# OpenBook.net
KiCad netlist of a schematic drawn in EAGLE
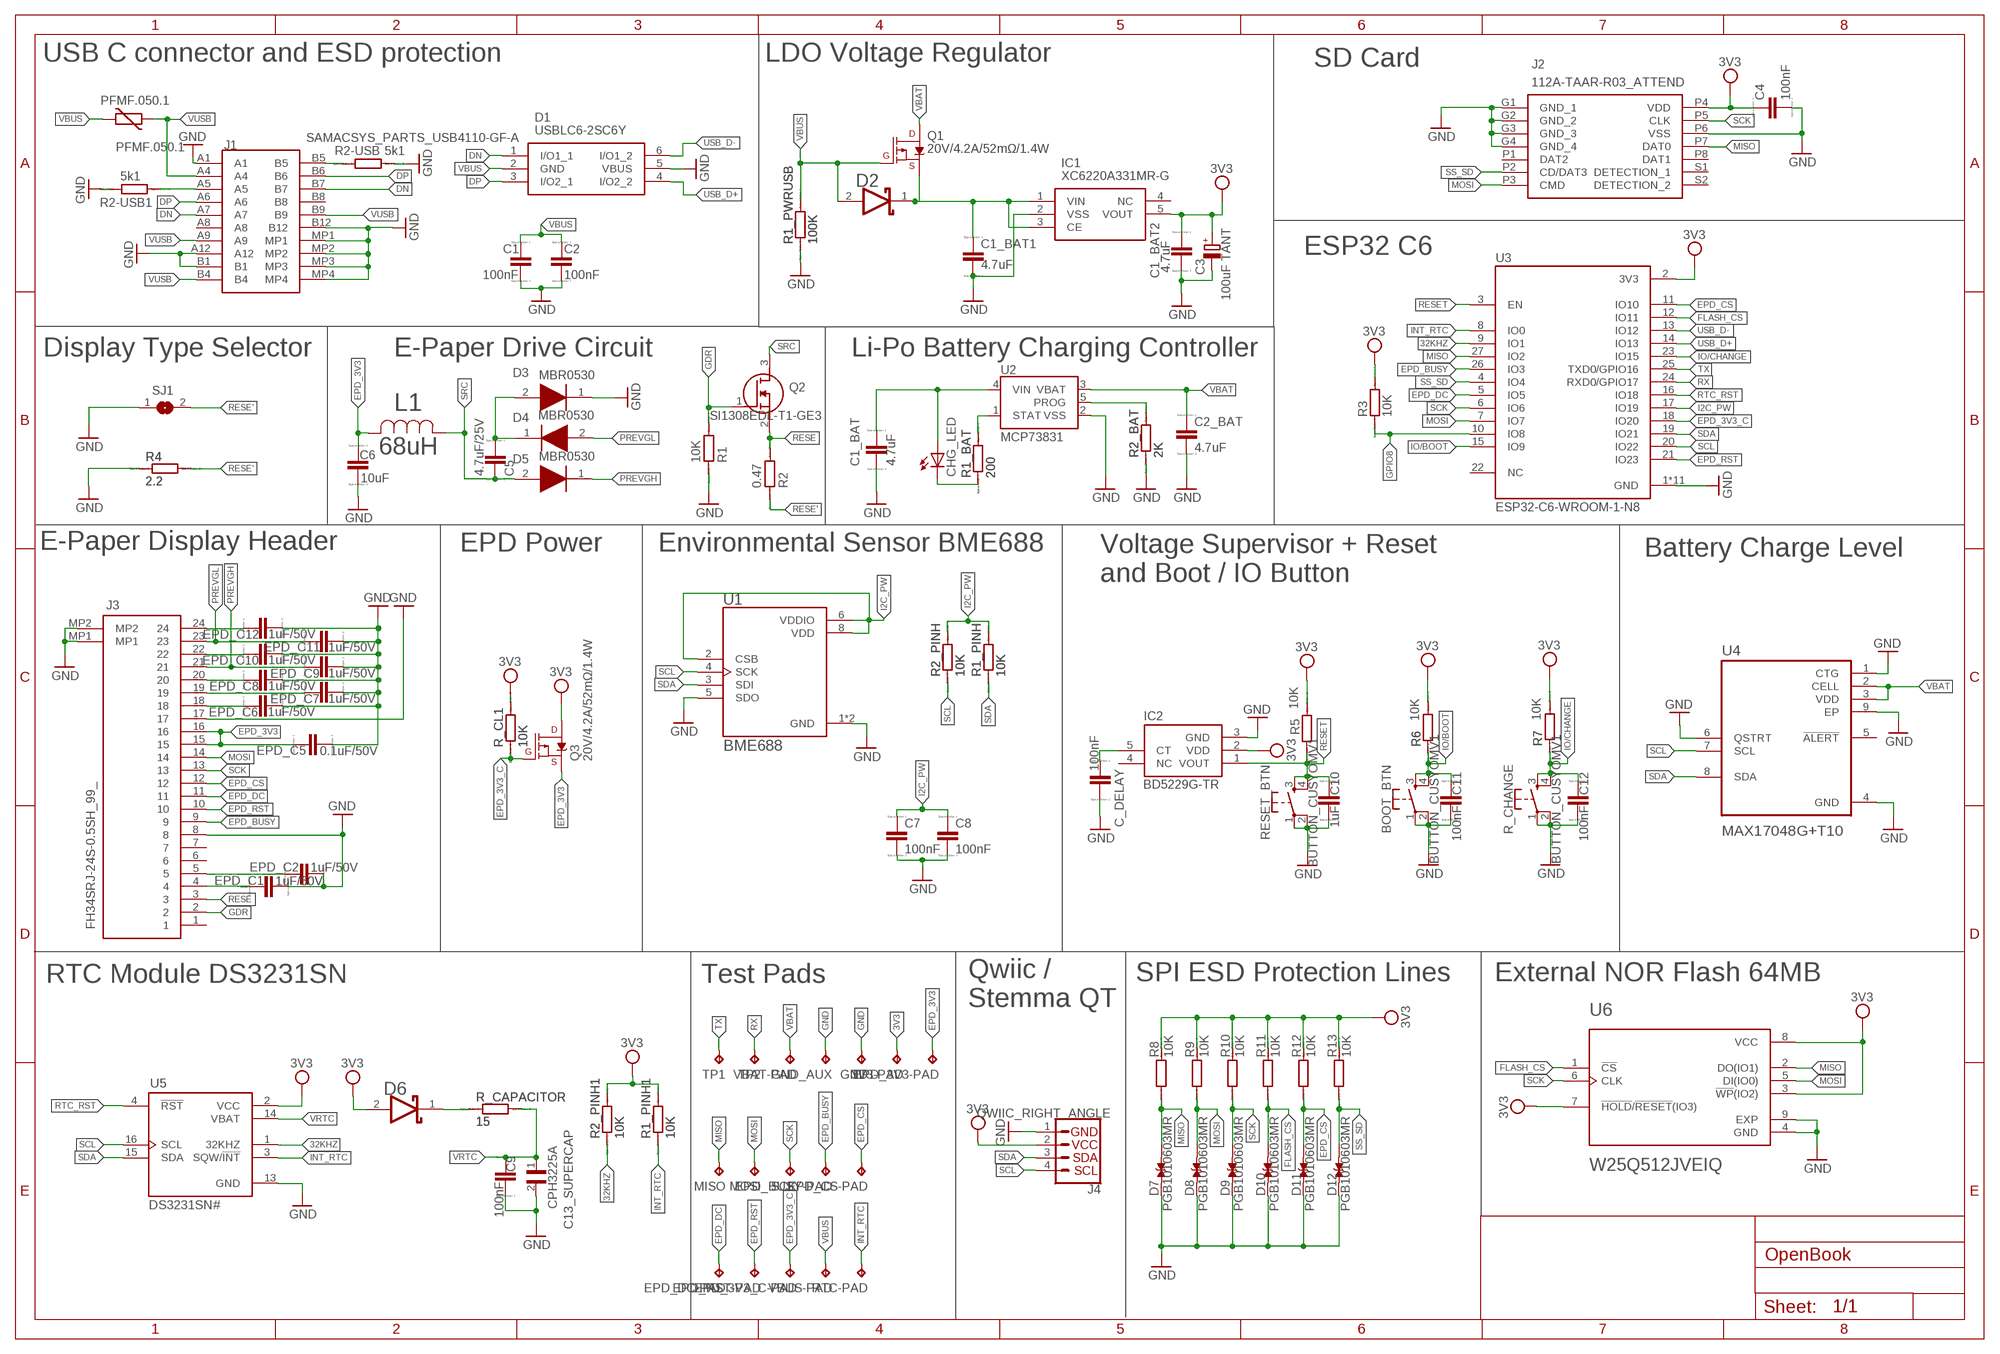
[diagram p0: schematic, sheet 1]

(export (version "E")
  (design (tool "Eeschema 10.0.6"))
  (components
    (comp (ref "3V3-PAD")
      (value "TPTP20R")
      (footprint "eagle-import:TP20R")
      (libsource (lib "eagle-import") (part "TPTP20R"))
    )
    (comp (ref "BOOT_BTN")
      (value "BUTTON_CUSYOMV1")
      (footprint "eagle-import:MYBUTTON")
      (libsource (lib "eagle-import") (part "BUTTON_CUSYOMV1"))
    )
    (comp (ref "C1")
      (value "100nF")
      (footprint "eagle-import:ESP32_WROVER_EAGLE-LTSPICE_C0402")
      (libsource (lib "eagle-import") (part "ESP32_WROVER_EAGLE-LTSPICE_CC0402"))
    )
    (comp (ref "C1_BAT")
      (value "4.7uF")
      (footprint "eagle-import:EAGLE-LTSPICE_C0402")
      (libsource (lib "eagle-import") (part "EAGLE-LTSPICE_CC0402"))
    )
    (comp (ref "C1_BAT1")
      (value "4.7uF")
      (footprint "eagle-import:EAGLE-LTSPICE_C0402")
      (libsource (lib "eagle-import") (part "EAGLE-LTSPICE_CC0402"))
    )
    (comp (ref "C1_BAT2")
      (value "4.7uF")
      (footprint "eagle-import:EAGLE-LTSPICE_C0402")
      (libsource (lib "eagle-import") (part "EAGLE-LTSPICE_CC0402"))
    )
    (comp (ref "C2")
      (value "100nF")
      (footprint "eagle-import:ESP32_WROVER_EAGLE-LTSPICE_C0402")
      (libsource (lib "eagle-import") (part "ESP32_WROVER_EAGLE-LTSPICE_CC0402"))
    )
    (comp (ref "C2_BAT")
      (value "4.7uF")
      (footprint "eagle-import:EAGLE-LTSPICE_C0402")
      (libsource (lib "eagle-import") (part "EAGLE-LTSPICE_CC0402"))
    )
    (comp (ref "C3")
      (value "100uF TANT")
      (footprint "eagle-import:RCL_CT3528")
      (libsource (lib "eagle-import") (part "RCL_CPOL-EUCT3528"))
    )
    (comp (ref "C4")
      (value "100nF")
      (footprint "eagle-import:EAGLE-LTSPICE_C0402")
      (libsource (lib "eagle-import") (part "EAGLE-LTSPICE_CC0402"))
    )
    (comp (ref "C5")
      (value "4.7uF/25V")
      (footprint "eagle-import:ESP32_WROVER_EAGLE-LTSPICE_C0402")
      (libsource (lib "eagle-import") (part "ESP32_WROVER_EAGLE-LTSPICE_CC0402"))
    )
    (comp (ref "C6")
      (value "10uF")
      (footprint "eagle-import:ESP32_WROVER_EAGLE-LTSPICE_C0402")
      (libsource (lib "eagle-import") (part "ESP32_WROVER_EAGLE-LTSPICE_CC0402"))
    )
    (comp (ref "C7")
      (value "100nF")
      (footprint "eagle-import:EAGLE-LTSPICE_C0402")
      (libsource (lib "eagle-import") (part "EAGLE-LTSPICE_CC0402"))
    )
    (comp (ref "C8")
      (value "100nF")
      (footprint "eagle-import:EAGLE-LTSPICE_C0402")
      (libsource (lib "eagle-import") (part "EAGLE-LTSPICE_CC0402"))
    )
    (comp (ref "C9")
      (value "100nF")
      (footprint "eagle-import:EAGLE-LTSPICE_C0402")
      (libsource (lib "eagle-import") (part "EAGLE-LTSPICE_CC0402"))
    )
    (comp (ref "C10")
      (value "1uF")
      (footprint "eagle-import:EAGLE-LTSPICE_C0402")
      (libsource (lib "eagle-import") (part "EAGLE-LTSPICE_CC0402"))
    )
    (comp (ref "C11")
      (value "100nF")
      (footprint "eagle-import:EAGLE-LTSPICE_C0402")
      (libsource (lib "eagle-import") (part "EAGLE-LTSPICE_CC0402"))
    )
    (comp (ref "C12")
      (value "100nF")
      (footprint "eagle-import:EAGLE-LTSPICE_C0402")
      (libsource (lib "eagle-import") (part "EAGLE-LTSPICE_CC0402"))
    )
    (comp (ref "C13_SUPERCAP")
      (value "CPH3225A")
      (footprint "eagle-import:CAPCP3225X100N")
      (fields (field (name "MF") "Seiko Instruments"))
      (libsource (lib "eagle-import") (part "CPH3225A"))
    )
    (comp (ref "CHG_LED")
      (value "ADAFRUIT_LEDCHIP-LED0603")
      (footprint "eagle-import:ADAFRUIT_CHIP-LED0603")
      (libsource (lib "eagle-import") (part "ADAFRUIT_LEDCHIP-LED0603"))
    )
    (comp (ref "C_DELAY")
      (value "100nF")
      (footprint "eagle-import:EAGLE-LTSPICE_C0402")
      (libsource (lib "eagle-import") (part "EAGLE-LTSPICE_CC0402"))
    )
    (comp (ref "D1")
      (value "USBLC6-2SC6Y")
      (footprint "eagle-import:SOT95P280X145-6N")
      (fields (field (name "MF") "STMicroelectronics"))
      (libsource (lib "eagle-import") (part "USBLC6-2SC6Y"))
    )
    (comp (ref "D2")
      (value "ESP32_WROVER_AVX---SD0805S020S1R0_AVX_SD0805S020S1R0_0_0AVX_SD0805S020S1R0_0_0")
      (footprint "eagle-import:ESP32_WROVER_AVX---SD0805S020S1R0_AVX_SD0805S020S1R0_0")
      (fields
        (field (name "DIGIKEY_PART_NUMBER") "478-7800-1-ND")
        (field (name "MF") "AVX")
        (field (name "MOUSER_PART_NUMBER") "581-SD0805S020S1R0")
      )
      (libsource (lib "eagle-import") (part "ESP32_WROVER_AVX---SD0805S020S1R0_AVX_SD0805S020S1R0_0_0AVX_SD0805S020S1R0_0_0"))
    )
    (comp (ref "D3")
      (value "MBR0530")
      (footprint "eagle-import:SOD3716X135N")
      (fields (field (name "MF") "ON Semiconductor"))
      (libsource (lib "eagle-import") (part "MBR0530"))
    )
    (comp (ref "D4")
      (value "MBR0530")
      (footprint "eagle-import:SOD3716X135N")
      (fields (field (name "MF") "ON Semiconductor"))
      (libsource (lib "eagle-import") (part "MBR0530"))
    )
    (comp (ref "D5")
      (value "MBR0530")
      (footprint "eagle-import:SOD3716X135N")
      (fields (field (name "MF") "ON Semiconductor"))
      (libsource (lib "eagle-import") (part "MBR0530"))
    )
    (comp (ref "D6")
      (value "ESP32_WROVER_AVX---SD0805S020S1R0_AVX_SD0805S020S1R0_0_0AVX_SD0805S020S1R0_0_0")
      (footprint "eagle-import:ESP32_WROVER_AVX---SD0805S020S1R0_AVX_SD0805S020S1R0_0")
      (fields
        (field (name "DIGIKEY_PART_NUMBER") "478-7800-1-ND")
        (field (name "MF") "AVX")
        (field (name "MOUSER_PART_NUMBER") "581-SD0805S020S1R0")
      )
      (libsource (lib "eagle-import") (part "ESP32_WROVER_AVX---SD0805S020S1R0_AVX_SD0805S020S1R0_0_0AVX_SD0805S020S1R0_0_0"))
    )
    (comp (ref "D7")
      (value "PGB1010603MR")
      (footprint "eagle-import:DIOC1608X36N")
      (fields (field (name "MF") "Littelfuse Inc."))
      (libsource (lib "eagle-import") (part "PGB1010603MR"))
    )
    (comp (ref "D8")
      (value "PGB1010603MR")
      (footprint "eagle-import:DIOC1608X36N")
      (fields (field (name "MF") "Littelfuse Inc."))
      (libsource (lib "eagle-import") (part "PGB1010603MR"))
    )
    (comp (ref "D9")
      (value "PGB1010603MR")
      (footprint "eagle-import:DIOC1608X36N")
      (fields (field (name "MF") "Littelfuse Inc."))
      (libsource (lib "eagle-import") (part "PGB1010603MR"))
    )
    (comp (ref "D10")
      (value "PGB1010603MR")
      (footprint "eagle-import:DIOC1608X36N")
      (fields (field (name "MF") "Littelfuse Inc."))
      (libsource (lib "eagle-import") (part "PGB1010603MR"))
    )
    (comp (ref "D11")
      (value "PGB1010603MR")
      (footprint "eagle-import:DIOC1608X36N")
      (fields (field (name "MF") "Littelfuse Inc."))
      (libsource (lib "eagle-import") (part "PGB1010603MR"))
    )
    (comp (ref "D12")
      (value "PGB1010603MR")
      (footprint "eagle-import:DIOC1608X36N")
      (fields (field (name "MF") "Littelfuse Inc."))
      (libsource (lib "eagle-import") (part "PGB1010603MR"))
    )
    (comp (ref "EPD_3V3-PAD")
      (value "TPTP20R")
      (footprint "eagle-import:TP20R")
      (libsource (lib "eagle-import") (part "TPTP20R"))
    )
    (comp (ref "EPD_3V3_C-PAD")
      (value "TPTP20R")
      (footprint "eagle-import:TP20R")
      (libsource (lib "eagle-import") (part "TPTP20R"))
    )
    (comp (ref "EPD_BUSY-PAD")
      (value "TPTP20R")
      (footprint "eagle-import:TP20R")
      (libsource (lib "eagle-import") (part "TPTP20R"))
    )
    (comp (ref "EPD_C1")
      (value "1uF/50V")
      (footprint "eagle-import:ESP32_WROVER_EAGLE-LTSPICE_C0402")
      (libsource (lib "eagle-import") (part "ESP32_WROVER_EAGLE-LTSPICE_CC0402"))
    )
    (comp (ref "EPD_C2")
      (value "1uF/50V")
      (footprint "eagle-import:ESP32_WROVER_EAGLE-LTSPICE_C0402")
      (libsource (lib "eagle-import") (part "ESP32_WROVER_EAGLE-LTSPICE_CC0402"))
    )
    (comp (ref "EPD_C5")
      (value "0.1uF/50V")
      (footprint "eagle-import:ESP32_WROVER_EAGLE-LTSPICE_C0402")
      (libsource (lib "eagle-import") (part "ESP32_WROVER_EAGLE-LTSPICE_CC0402"))
    )
    (comp (ref "EPD_C6")
      (value "1uF/50V")
      (footprint "eagle-import:ESP32_WROVER_EAGLE-LTSPICE_C0402")
      (libsource (lib "eagle-import") (part "ESP32_WROVER_EAGLE-LTSPICE_CC0402"))
    )
    (comp (ref "EPD_C7")
      (value "1uF/50V")
      (footprint "eagle-import:ESP32_WROVER_EAGLE-LTSPICE_C0402")
      (libsource (lib "eagle-import") (part "ESP32_WROVER_EAGLE-LTSPICE_CC0402"))
    )
    (comp (ref "EPD_C8")
      (value "1uF/50V")
      (footprint "eagle-import:ESP32_WROVER_EAGLE-LTSPICE_C0402")
      (libsource (lib "eagle-import") (part "ESP32_WROVER_EAGLE-LTSPICE_CC0402"))
    )
    (comp (ref "EPD_C9")
      (value "1uF/50V")
      (footprint "eagle-import:ESP32_WROVER_EAGLE-LTSPICE_C0402")
      (libsource (lib "eagle-import") (part "ESP32_WROVER_EAGLE-LTSPICE_CC0402"))
    )
    (comp (ref "EPD_C10")
      (value "1uF/50V")
      (footprint "eagle-import:ESP32_WROVER_EAGLE-LTSPICE_C0402")
      (libsource (lib "eagle-import") (part "ESP32_WROVER_EAGLE-LTSPICE_CC0402"))
    )
    (comp (ref "EPD_C11")
      (value "1uF/50V")
      (footprint "eagle-import:ESP32_WROVER_EAGLE-LTSPICE_C0402")
      (libsource (lib "eagle-import") (part "ESP32_WROVER_EAGLE-LTSPICE_CC0402"))
    )
    (comp (ref "EPD_C12")
      (value "1uF/50V")
      (footprint "eagle-import:ESP32_WROVER_EAGLE-LTSPICE_C0402")
      (libsource (lib "eagle-import") (part "ESP32_WROVER_EAGLE-LTSPICE_CC0402"))
    )
    (comp (ref "EPD_CS-PAD")
      (value "TPTP20R")
      (footprint "eagle-import:TP20R")
      (libsource (lib "eagle-import") (part "TPTP20R"))
    )
    (comp (ref "EPD_DC-PAD")
      (value "TPTP20R")
      (footprint "eagle-import:TP20R")
      (libsource (lib "eagle-import") (part "TPTP20R"))
    )
    (comp (ref "EPD_RST-PAD")
      (value "TPTP20R")
      (footprint "eagle-import:TP20R")
      (libsource (lib "eagle-import") (part "TPTP20R"))
    )
    (comp (ref "GND")
      (value "TPTP20R")
      (footprint "eagle-import:TP20R")
      (libsource (lib "eagle-import") (part "TPTP20R"))
    )
    (comp (ref "GND_AUX")
      (value "TPTP20R")
      (footprint "eagle-import:TP20R")
      (libsource (lib "eagle-import") (part "TPTP20R"))
    )
    (comp (ref "IC1")
      (value "XC6220A331MR-G")
      (footprint "eagle-import:SOT95P280X120-5N")
      (fields (field (name "MOUSER_PART_NUMBER") "865-XC6220A331MR-G"))
      (libsource (lib "eagle-import") (part "XC6220A331MR-G"))
    )
    (comp (ref "IC2")
      (value "BD5229G-TR")
      (footprint "eagle-import:SOT95P280X125-5N")
      (fields (field (name "MOUSER_PART_NUMBER") "755-BD5229G-TR"))
      (libsource (lib "eagle-import") (part "BD5229G-TR"))
    )
    (comp (ref "J1")
      (value "SAMACSYS_PARTS_USB4110-GF-A")
      (footprint "eagle-import:SAMACSYS_PARTS_USB4110GFA")
      (fields
        (field (name "MANUFACTURER_PART_NUMBER") "USB4110-GF-A")
        (field (name "MOUSER_PART_NUMBER") "640-USB4110-GF-A")
      )
      (libsource (lib "eagle-import") (part "SAMACSYS_PARTS_USB4110-GF-A"))
    )
    (comp (ref "J2")
      (value "112A-TAAR-R03_ATTEND")
      (footprint "eagle-import:112ATAARR03ATTEND")
      (fields (field (name "MANUFACTURER_PART_NUMBER") "112A-TAAR-R03 ATTEND"))
      (libsource (lib "eagle-import") (part "112A-TAAR-R03_ATTEND"))
    )
    (comp (ref "J3")
      (value "FH34SRJ-24S-0.5SH_99_")
      (footprint "eagle-import:FH34SRJ24S05SH99")
      (fields
        (field (name "MANUFACTURER_PART_NUMBER") "FH34SRJ-24S-0.5SH(99)")
        (field (name "MOUSER_PART_NUMBER") "798-FH34SRJ24S05SH99")
      )
      (libsource (lib "eagle-import") (part "FH34SRJ-24S-0.5SH_99_"))
    )
    (comp (ref "J4")
      (value "QWIIC_RIGHT_ANGLE")
      (footprint "eagle-import:JST04_1MM_RA")
      (libsource (lib "eagle-import") (part "QWIIC_CONNECTORJS-1MM"))
    )
    (comp (ref "L1")
      (value "68uH")
      (footprint "eagle-import:IND_4828-WE-TPC_WRE")
      (fields
        (field (name "MANUFACTURER_PART_NUMBER") "744043680")
        (field (name "COPYRIGHT") "Copyright (C) 2024 Ultra Librarian. All rights reserved.")
      )
      (libsource (lib "eagle-import") (part "744043680IND_4828-WE-TPC_WRE"))
    )
    (comp (ref "MISO")
      (value "TPTP20R")
      (footprint "eagle-import:TP20R")
      (libsource (lib "eagle-import") (part "TPTP20R"))
    )
    (comp (ref "MOSI")
      (value "TPTP20R")
      (footprint "eagle-import:TP20R")
      (libsource (lib "eagle-import") (part "TPTP20R"))
    )
    (comp (ref "PFMF.050.1")
      (value "PFMF.050.1")
      (footprint "eagle-import:ESP32C6_VARISTOR_CT_CN1812")
      (libsource (lib "eagle-import") (part "ESP32C6_VARISTORCN1812"))
    )
    (comp (ref "Q1")
      (value "20V/4.2A/52mΩ/1.4W")
      (footprint "eagle-import:ESP32_WROVER_SPARKFUN-DISCRETESEMI_SOT23-3")
      (libsource (lib "eagle-import") (part "ESP32_WROVER_SPARKFUN-DISCRETESEMI_MOSFET_PCH-DMG2305UX-7"))
    )
    (comp (ref "Q2")
      (value "SI1308EDL-T1-GE3")
      (footprint "eagle-import:SOT65P210X110-3N")
      (fields (field (name "MF") "Vishay Siliconix"))
      (libsource (lib "eagle-import") (part "SI1308EDL-T1-GE3"))
    )
    (comp (ref "Q3")
      (value "20V/4.2A/52mΩ/1.4W")
      (footprint "eagle-import:ESP32_WROVER_SPARKFUN-DISCRETESEMI_SOT23-3")
      (libsource (lib "eagle-import") (part "ESP32_WROVER_SPARKFUN-DISCRETESEMI_MOSFET_PCH-DMG2305UX-7"))
    )
    (comp (ref "R1")
      (value "10K")
      (footprint "eagle-import:ESP32_WROVER_EAGLE-LTSPICE_R0402")
      (libsource (lib "eagle-import") (part "ESP32_WROVER_EAGLE-LTSPICE_RR0402"))
    )
    (comp (ref "R1_BAT")
      (value "200")
      (footprint "eagle-import:ESP32_WROVER_EAGLE-LTSPICE_R0402")
      (libsource (lib "eagle-import") (part "ESP32_WROVER_EAGLE-LTSPICE_RR0402"))
    )
    (comp (ref "R1_PINH")
      (value "10K")
      (footprint "eagle-import:ESP32_WROVER_EAGLE-LTSPICE_R0402")
      (libsource (lib "eagle-import") (part "ESP32_WROVER_EAGLE-LTSPICE_RR0402"))
    )
    (comp (ref "R1_PINH1")
      (value "10K")
      (footprint "eagle-import:ESP32_WROVER_EAGLE-LTSPICE_R0402")
      (libsource (lib "eagle-import") (part "ESP32_WROVER_EAGLE-LTSPICE_RR0402"))
    )
    (comp (ref "R1_PWRUSB")
      (value "100K")
      (footprint "eagle-import:ESP32_WROVER_EAGLE-LTSPICE_R0402")
      (libsource (lib "eagle-import") (part "ESP32_WROVER_EAGLE-LTSPICE_RR0402"))
    )
    (comp (ref "R2")
      (value "0.47")
      (footprint "eagle-import:ESP32_WROVER_EAGLE-LTSPICE_R0402")
      (libsource (lib "eagle-import") (part "ESP32_WROVER_EAGLE-LTSPICE_RR0402"))
    )
    (comp (ref "R2-USB")
      (value "5k1")
      (footprint "eagle-import:ESP32_WROVER_EAGLE-LTSPICE_R0402")
      (libsource (lib "eagle-import") (part "ESP32_WROVER_EAGLE-LTSPICE_RR0402"))
    )
    (comp (ref "R2-USB1")
      (value "5k1")
      (footprint "eagle-import:ESP32_WROVER_EAGLE-LTSPICE_R0402")
      (libsource (lib "eagle-import") (part "ESP32_WROVER_EAGLE-LTSPICE_RR0402"))
    )
    (comp (ref "R2_BAT")
      (value "2K")
      (footprint "eagle-import:ESP32_WROVER_EAGLE-LTSPICE_R0402")
      (libsource (lib "eagle-import") (part "ESP32_WROVER_EAGLE-LTSPICE_RR0402"))
    )
    (comp (ref "R2_PINH")
      (value "10K")
      (footprint "eagle-import:ESP32_WROVER_EAGLE-LTSPICE_R0402")
      (libsource (lib "eagle-import") (part "ESP32_WROVER_EAGLE-LTSPICE_RR0402"))
    )
    (comp (ref "R2_PINH1")
      (value "10K")
      (footprint "eagle-import:ESP32_WROVER_EAGLE-LTSPICE_R0402")
      (libsource (lib "eagle-import") (part "ESP32_WROVER_EAGLE-LTSPICE_RR0402"))
    )
    (comp (ref "R3")
      (value "10K")
      (footprint "eagle-import:ESP32_WROVER_EAGLE-LTSPICE_R0402")
      (libsource (lib "eagle-import") (part "ESP32_WROVER_EAGLE-LTSPICE_RR0402"))
    )
    (comp (ref "R4")
      (value "2.2")
      (footprint "eagle-import:ESP32_WROVER_EAGLE-LTSPICE_R0402")
      (libsource (lib "eagle-import") (part "ESP32_WROVER_EAGLE-LTSPICE_RR0402"))
    )
    (comp (ref "R5")
      (value "10K")
      (footprint "eagle-import:ESP32_WROVER_EAGLE-LTSPICE_R0402")
      (libsource (lib "eagle-import") (part "ESP32_WROVER_EAGLE-LTSPICE_RR0402"))
    )
    (comp (ref "R6")
      (value "10K")
      (footprint "eagle-import:ESP32_WROVER_EAGLE-LTSPICE_R0402")
      (libsource (lib "eagle-import") (part "ESP32_WROVER_EAGLE-LTSPICE_RR0402"))
    )
    (comp (ref "R7")
      (value "10K")
      (footprint "eagle-import:ESP32_WROVER_EAGLE-LTSPICE_R0402")
      (libsource (lib "eagle-import") (part "ESP32_WROVER_EAGLE-LTSPICE_RR0402"))
    )
    (comp (ref "R8")
      (value "10K")
      (footprint "eagle-import:ESP32_WROVER_EAGLE-LTSPICE_R0402")
      (libsource (lib "eagle-import") (part "ESP32_WROVER_EAGLE-LTSPICE_RR0402"))
    )
    (comp (ref "R9")
      (value "10K")
      (footprint "eagle-import:ESP32_WROVER_EAGLE-LTSPICE_R0402")
      (libsource (lib "eagle-import") (part "ESP32_WROVER_EAGLE-LTSPICE_RR0402"))
    )
    (comp (ref "R10")
      (value "10K")
      (footprint "eagle-import:ESP32_WROVER_EAGLE-LTSPICE_R0402")
      (libsource (lib "eagle-import") (part "ESP32_WROVER_EAGLE-LTSPICE_RR0402"))
    )
    (comp (ref "R11")
      (value "10K")
      (footprint "eagle-import:ESP32_WROVER_EAGLE-LTSPICE_R0402")
      (libsource (lib "eagle-import") (part "ESP32_WROVER_EAGLE-LTSPICE_RR0402"))
    )
    (comp (ref "R12")
      (value "10K")
      (footprint "eagle-import:ESP32_WROVER_EAGLE-LTSPICE_R0402")
      (libsource (lib "eagle-import") (part "ESP32_WROVER_EAGLE-LTSPICE_RR0402"))
    )
    (comp (ref "R13")
      (value "10K")
      (footprint "eagle-import:ESP32_WROVER_EAGLE-LTSPICE_R0402")
      (libsource (lib "eagle-import") (part "ESP32_WROVER_EAGLE-LTSPICE_RR0402"))
    )
    (comp (ref "RESET_BTN")
      (value "BUTTON_CUSYOMV1")
      (footprint "eagle-import:MYBUTTON")
      (libsource (lib "eagle-import") (part "BUTTON_CUSYOMV1"))
    )
    (comp (ref "RTC-PAD")
      (value "TPTP20R")
      (footprint "eagle-import:TP20R")
      (libsource (lib "eagle-import") (part "TPTP20R"))
    )
    (comp (ref "R_CAPACITOR")
      (value "15")
      (footprint "eagle-import:ESP32_WROVER_EAGLE-LTSPICE_R0402")
      (libsource (lib "eagle-import") (part "ESP32_WROVER_EAGLE-LTSPICE_RR0402"))
    )
    (comp (ref "R_CHANGE")
      (value "BUTTON_CUSYOMV1")
      (footprint "eagle-import:MYBUTTON")
      (libsource (lib "eagle-import") (part "BUTTON_CUSYOMV1"))
    )
    (comp (ref "R_CL1")
      (value "10K")
      (footprint "eagle-import:ESP32_WROVER_EAGLE-LTSPICE_R0402")
      (libsource (lib "eagle-import") (part "ESP32_WROVER_EAGLE-LTSPICE_RR0402"))
    )
    (comp (ref "SCK")
      (value "TPTP20R")
      (footprint "eagle-import:TP20R")
      (libsource (lib "eagle-import") (part "TPTP20R"))
    )
    (comp (ref "SJ1") (value "SJ") (footprint "eagle-import:SJ") (libsource (lib "eagle-import") (part "SJ")))
    (comp (ref "TP1")
      (value "TPTP20R")
      (footprint "eagle-import:TP20R")
      (libsource (lib "eagle-import") (part "TPTP20R"))
    )
    (comp (ref "TP2")
      (value "TPTP20R")
      (footprint "eagle-import:TP20R")
      (libsource (lib "eagle-import") (part "TPTP20R"))
    )
    (comp (ref "U1")
      (value "BME688")
      (footprint "eagle-import:ESP32_WROVER_BME680_PSON80P300X300X100-8N")
      (fields (field (name "MF") "Bosch Sensortec") (field (name "MP") "BME680"))
      (libsource (lib "eagle-import") (part "ESP32_WROVER_BME680_BME680"))
    )
    (comp (ref "U2")
      (value "MCP73831")
      (footprint "eagle-import:ESP32_WROVER_SPARKFUN-IC-POWER_SOT23-5")
      (libsource (lib "eagle-import") (part "ESP32_WROVER_SPARKFUN-IC-POWER_MCP73831"))
    )
    (comp (ref "U3")
      (value "ESP32-C6-WROOM-1-N8")
      (footprint "eagle-import:XCVR_ESP32-C6-WROOM-1-N8")
      (fields (field (name "MF") "Espressif Systems"))
      (libsource (lib "eagle-import") (part "ESP32-C6-WROOM-1-N8"))
    )
    (comp (ref "U4")
      (value "MAX17048G+T10")
      (footprint "eagle-import:SON50P200X200X80-9N")
      (fields (field (name "MF") "Analog Devices"))
      (libsource (lib "eagle-import") (part "MAX17048G+T10"))
    )
    (comp (ref "U5")
      (value "DS3231SN#")
      (footprint "eagle-import:SOIC127P1032X265-16N")
      (fields (field (name "MF") "Analog Devices"))
      (libsource (lib "eagle-import") (part "DS3231SN#"))
    )
    (comp (ref "U6")
      (value "W25Q512JVEIQ")
      (footprint "eagle-import:SON127P600X800X80-9N")
      (fields (field (name "MF") "Winbond Electronics"))
      (libsource (lib "eagle-import") (part "W25Q512JVEIQ"))
    )
    (comp (ref "VBAT-PAD")
      (value "TPTP20R")
      (footprint "eagle-import:TP20R")
      (libsource (lib "eagle-import") (part "TPTP20R"))
    )
    (comp (ref "VBUS-PAD")
      (value "TPTP20R")
      (footprint "eagle-import:TP20R")
      (libsource (lib "eagle-import") (part "TPTP20R"))
    )
  )
  (nets
    (net (code "1") (name "3V3") (class "Default")
      (node (ref "3V3-PAD") (pin "TP") (pinfunction "TP_TP") (pintype "input"))
      (node (ref "C1_BAT2") (pin "1") (pinfunction "1_1") (pintype "passive"))
      (node (ref "C3") (pin "+") (pinfunction "+_+") (pintype "passive"))
      (node (ref "C4") (pin "1") (pinfunction "1_1") (pintype "passive"))
      (node (ref "D6") (pin "2") (pinfunction "ANODE_2") (pintype "bidirectional"))
      (node (ref "IC1") (pin "5") (pinfunction "VOUT_5") (pintype "bidirectional"))
      (node (ref "IC2") (pin "2") (pinfunction "VDD_2") (pintype "bidirectional"))
      (node (ref "J2") (pin "P4") (pinfunction "VDD_P4") (pintype "bidirectional"))
      (node (ref "J4") (pin "2") (pinfunction "2_2") (pintype "power_in"))
      (node (ref "Q3") (pin "3") (pinfunction "D_3") (pintype "bidirectional"))
      (node (ref "R10") (pin "2") (pinfunction "2_2") (pintype "passive"))
      (node (ref "R11") (pin "2") (pinfunction "2_2") (pintype "passive"))
      (node (ref "R12") (pin "2") (pinfunction "2_2") (pintype "passive"))
      (node (ref "R13") (pin "2") (pinfunction "2_2") (pintype "passive"))
      (node (ref "R1_PINH1") (pin "2") (pinfunction "2_2") (pintype "passive"))
      (node (ref "R2_PINH1") (pin "2") (pinfunction "2_2") (pintype "passive"))
      (node (ref "R3") (pin "2") (pinfunction "2_2") (pintype "passive"))
      (node (ref "R5") (pin "2") (pinfunction "2_2") (pintype "passive"))
      (node (ref "R6") (pin "2") (pinfunction "2_2") (pintype "passive"))
      (node (ref "R7") (pin "2") (pinfunction "2_2") (pintype "passive"))
      (node (ref "R8") (pin "2") (pinfunction "2_2") (pintype "passive"))
      (node (ref "R9") (pin "2") (pinfunction "2_2") (pintype "passive"))
      (node (ref "R_CL1") (pin "2") (pinfunction "2_2") (pintype "passive"))
      (node (ref "U3") (pin "2") (pinfunction "3V3_2") (pintype "power_in"))
      (node (ref "U5") (pin "2") (pinfunction "VCC_2") (pintype "power_in"))
      (node (ref "U6") (pin "3") (pinfunction "~{WP}(IO2)_3") (pintype "bidirectional"))
      (node (ref "U6") (pin "7") (pinfunction "~{HOLD}/~{RESET}(IO3)_7") (pintype "bidirectional"))
      (node (ref "U6") (pin "8") (pinfunction "VCC_8") (pintype "power_in"))
    )
    (net (code "2") (name "32KHZ") (class "Default")
      (node (ref "R2_PINH1") (pin "1") (pinfunction "1_1") (pintype "passive"))
      (node (ref "U3") (pin "9") (pinfunction "IO1_9") (pintype "bidirectional"))
      (node (ref "U5") (pin "1") (pinfunction "32KHZ_1") (pintype "output"))
    )
    (net (code "3") (name "DN") (class "Default")
      (node (ref "D1") (pin "1") (pinfunction "I/O1_1_1") (pintype "bidirectional"))
      (node (ref "J1") (pin "A7") (pinfunction "A7_A7") (pintype "bidirectional"))
      (node (ref "J1") (pin "B7") (pinfunction "B7_B7") (pintype "bidirectional"))
    )
    (net (code "4") (name "DP") (class "Default")
      (node (ref "D1") (pin "3") (pinfunction "I/O2_1_3") (pintype "bidirectional"))
      (node (ref "J1") (pin "A6") (pinfunction "A6_A6") (pintype "bidirectional"))
      (node (ref "J1") (pin "B6") (pinfunction "B6_B6") (pintype "bidirectional"))
    )
    (net (code "5") (name "EPD_3V3") (class "Default")
      (node (ref "C6") (pin "1") (pinfunction "1_1") (pintype "passive"))
      (node (ref "EPD_3V3-PAD") (pin "TP") (pinfunction "TP_TP") (pintype "input"))
      (node (ref "EPD_C5") (pin "1") (pinfunction "1_1") (pintype "passive"))
      (node (ref "J3") (pin "15") (pinfunction "15_15") (pintype "bidirectional"))
      (node (ref "J3") (pin "16") (pinfunction "16_16") (pintype "bidirectional"))
      (node (ref "L1") (pin "2") (pinfunction "2_2") (pintype "passive"))
      (node (ref "Q3") (pin "2") (pinfunction "S_2") (pintype "bidirectional"))
    )
    (net (code "6") (name "EPD_3V3_C") (class "Default")
      (node (ref "EPD_3V3_C-PAD") (pin "TP") (pinfunction "TP_TP") (pintype "input"))
      (node (ref "Q3") (pin "1") (pinfunction "G_1") (pintype "bidirectional"))
      (node (ref "R_CL1") (pin "1") (pinfunction "1_1") (pintype "passive"))
      (node (ref "U3") (pin "18") (pinfunction "IO20_18") (pintype "bidirectional"))
    )
    (net (code "7") (name "EPD_BUSY") (class "Default")
      (node (ref "EPD_BUSY-PAD") (pin "TP") (pinfunction "TP_TP") (pintype "input"))
      (node (ref "J3") (pin "9") (pinfunction "9_9") (pintype "bidirectional"))
      (node (ref "U3") (pin "26") (pinfunction "IO3_26") (pintype "bidirectional"))
    )
    (net (code "8") (name "EPD_CS") (class "Default")
      (node (ref "D11") (pin "2") (pinfunction "2_2") (pintype "passive"))
      (node (ref "EPD_CS-PAD") (pin "TP") (pinfunction "TP_TP") (pintype "input"))
      (node (ref "J3") (pin "12") (pinfunction "12_12") (pintype "bidirectional"))
      (node (ref "R12") (pin "1") (pinfunction "1_1") (pintype "passive"))
      (node (ref "U3") (pin "11") (pinfunction "IO10_11") (pintype "bidirectional"))
    )
    (net (code "9") (name "EPD_DC") (class "Default")
      (node (ref "EPD_DC-PAD") (pin "TP") (pinfunction "TP_TP") (pintype "input"))
      (node (ref "J3") (pin "11") (pinfunction "11_11") (pintype "bidirectional"))
      (node (ref "U3") (pin "5") (pinfunction "IO5_5") (pintype "bidirectional"))
    )
    (net (code "10") (name "EPD_RST") (class "Default")
      (node (ref "EPD_RST-PAD") (pin "TP") (pinfunction "TP_TP") (pintype "input"))
      (node (ref "J3") (pin "10") (pinfunction "10_10") (pintype "bidirectional"))
      (node (ref "U3") (pin "21") (pinfunction "IO23_21") (pintype "bidirectional"))
    )
    (net (code "11") (name "FLASH_CS") (class "Default")
      (node (ref "D10") (pin "2") (pinfunction "2_2") (pintype "passive"))
      (node (ref "R11") (pin "1") (pinfunction "1_1") (pintype "passive"))
      (node (ref "U3") (pin "12") (pinfunction "IO11_12") (pintype "bidirectional"))
      (node (ref "U6") (pin "1") (pinfunction "~{CS}_1") (pintype "input"))
    )
    (net (code "12") (name "GDR") (class "Default")
      (node (ref "J3") (pin "2") (pinfunction "2_2") (pintype "bidirectional"))
      (node (ref "Q2") (pin "1") (pinfunction "G_1") (pintype "bidirectional"))
      (node (ref "R1") (pin "2") (pinfunction "2_2") (pintype "passive"))
    )
    (net (code "13") (name "GND") (class "Default")
      (node (ref "BOOT_BTN") (pin "1") (pinfunction "1_1") (pintype "passive"))
      (node (ref "BOOT_BTN") (pin "2") (pinfunction "2_2") (pintype "passive"))
      (node (ref "C1") (pin "2") (pinfunction "2_2") (pintype "passive"))
      (node (ref "C10") (pin "2") (pinfunction "2_2") (pintype "passive"))
      (node (ref "C11") (pin "2") (pinfunction "2_2") (pintype "passive"))
      (node (ref "C12") (pin "2") (pinfunction "2_2") (pintype "passive"))
      (node (ref "C13_SUPERCAP") (pin "2") (pinfunction "2_2") (pintype "passive"))
      (node (ref "C1_BAT") (pin "2") (pinfunction "2_2") (pintype "passive"))
      (node (ref "C1_BAT1") (pin "2") (pinfunction "2_2") (pintype "passive"))
      (node (ref "C1_BAT2") (pin "2") (pinfunction "2_2") (pintype "passive"))
      (node (ref "C2") (pin "2") (pinfunction "2_2") (pintype "passive"))
      (node (ref "C2_BAT") (pin "2") (pinfunction "2_2") (pintype "passive"))
      (node (ref "C3") (pin "-") (pinfunction "-_-") (pintype "passive"))
      (node (ref "C4") (pin "2") (pinfunction "2_2") (pintype "passive"))
      (node (ref "C6") (pin "2") (pinfunction "2_2") (pintype "passive"))
      (node (ref "C7") (pin "2") (pinfunction "2_2") (pintype "passive"))
      (node (ref "C8") (pin "2") (pinfunction "2_2") (pintype "passive"))
      (node (ref "C9") (pin "2") (pinfunction "2_2") (pintype "passive"))
      (node (ref "C_DELAY") (pin "2") (pinfunction "2_2") (pintype "passive"))
      (node (ref "D1") (pin "5") (pinfunction "VBUS_5") (pintype "bidirectional"))
      (node (ref "D10") (pin "1") (pinfunction "1_1") (pintype "passive"))
      (node (ref "D11") (pin "1") (pinfunction "1_1") (pintype "passive"))
      (node (ref "D12") (pin "1") (pinfunction "1_1") (pintype "passive"))
      (node (ref "D3") (pin "1") (pinfunction "K_1") (pintype "bidirectional"))
      (node (ref "D7") (pin "1") (pinfunction "1_1") (pintype "passive"))
      (node (ref "D8") (pin "1") (pinfunction "1_1") (pintype "passive"))
      (node (ref "D9") (pin "1") (pinfunction "1_1") (pintype "passive"))
      (node (ref "EPD_C1") (pin "1") (pinfunction "1_1") (pintype "passive"))
      (node (ref "EPD_C10") (pin "2") (pinfunction "2_2") (pintype "passive"))
      (node (ref "EPD_C11") (pin "2") (pinfunction "2_2") (pintype "passive"))
      (node (ref "EPD_C12") (pin "2") (pinfunction "2_2") (pintype "passive"))
      (node (ref "EPD_C2") (pin "1") (pinfunction "1_1") (pintype "passive"))
      (node (ref "EPD_C5") (pin "2") (pinfunction "2_2") (pintype "passive"))
      (node (ref "EPD_C6") (pin "2") (pinfunction "2_2") (pintype "passive"))
      (node (ref "EPD_C7") (pin "2") (pinfunction "2_2") (pintype "passive"))
      (node (ref "EPD_C8") (pin "2") (pinfunction "2_2") (pintype "passive"))
      (node (ref "EPD_C9") (pin "2") (pinfunction "2_2") (pintype "passive"))
      (node (ref "GND") (pin "TP") (pinfunction "TP_TP") (pintype "input"))
      (node (ref "GND_AUX") (pin "TP") (pinfunction "TP_TP") (pintype "input"))
      (node (ref "IC1") (pin "2") (pinfunction "VSS_2") (pintype "bidirectional"))
      (node (ref "IC2") (pin "3") (pinfunction "GND_3") (pintype "bidirectional"))
      (node (ref "J1") (pin "A1") (pinfunction "A1_A1") (pintype "bidirectional"))
      (node (ref "J1") (pin "A12") (pinfunction "A12_A12") (pintype "bidirectional"))
      (node (ref "J1") (pin "B1") (pinfunction "B1_B1") (pintype "bidirectional"))
      (node (ref "J1") (pin "B12") (pinfunction "B12_B12") (pintype "bidirectional"))
      (node (ref "J1") (pin "MP1") (pinfunction "MP1_MP1") (pintype "bidirectional"))
      (node (ref "J1") (pin "MP2") (pinfunction "MP2_MP2") (pintype "bidirectional"))
      (node (ref "J1") (pin "MP3") (pinfunction "MP3_MP3") (pintype "bidirectional"))
      (node (ref "J1") (pin "MP4") (pinfunction "MP4_MP4") (pintype "bidirectional"))
      (node (ref "J2") (pin "G1") (pinfunction "GND_1_G1") (pintype "bidirectional"))
      (node (ref "J2") (pin "G2") (pinfunction "GND_2_G2") (pintype "bidirectional"))
      (node (ref "J2") (pin "G3") (pinfunction "GND_3_G3") (pintype "bidirectional"))
      (node (ref "J2") (pin "G4") (pinfunction "GND_4_G4") (pintype "bidirectional"))
      (node (ref "J2") (pin "P6") (pinfunction "VSS_P6") (pintype "bidirectional"))
      (node (ref "J3") (pin "17") (pinfunction "17_17") (pintype "bidirectional"))
      (node (ref "J3") (pin "8") (pinfunction "8_8") (pintype "bidirectional"))
      (node (ref "J3") (pin "MP1") (pinfunction "MP1_MP1") (pintype "bidirectional"))
      (node (ref "J3") (pin "MP2") (pinfunction "MP2_MP2") (pintype "bidirectional"))
      (node (ref "J4") (pin "1") (pinfunction "1_1") (pintype "power_in"))
      (node (ref "R1") (pin "1") (pinfunction "1_1") (pintype "passive"))
      (node (ref "R1_PWRUSB") (pin "1") (pinfunction "1_1") (pintype "passive"))
      (node (ref "R2-USB") (pin "2") (pinfunction "2_2") (pintype "passive"))
      (node (ref "R2-USB1") (pin "1") (pinfunction "1_1") (pintype "passive"))
      (node (ref "R2_BAT") (pin "1") (pinfunction "1_1") (pintype "passive"))
      (node (ref "R4") (pin "1") (pinfunction "1_1") (pintype "passive"))
      (node (ref "RESET_BTN") (pin "1") (pinfunction "1_1") (pintype "passive"))
      (node (ref "RESET_BTN") (pin "2") (pinfunction "2_2") (pintype "passive"))
      (node (ref "R_CHANGE") (pin "1") (pinfunction "1_1") (pintype "passive"))
      (node (ref "R_CHANGE") (pin "2") (pinfunction "2_2") (pintype "passive"))
      (node (ref "SJ1") (pin "1") (pinfunction "1_1") (pintype "passive"))
      (node (ref "U1") (pin "1") (pinfunction "GND_1") (pintype "power_in"))
      (node (ref "U1") (pin "5") (pinfunction "SDO_5") (pintype "bidirectional"))
      (node (ref "U1") (pin "7") (pinfunction "GND_7") (pintype "power_in"))
      (node (ref "U2") (pin "2") (pinfunction "VSS_2") (pintype "power_in"))
      (node (ref "U3") (pin "1") (pinfunction "GND_1") (pintype "power_in"))
      (node (ref "U3") (pin "28") (pinfunction "GND_28") (pintype "power_in"))
      (node (ref "U3") (pin "29_1") (pinfunction "GND_29_1") (pintype "power_in"))
      (node (ref "U3") (pin "29_2") (pinfunction "GND_29_2") (pintype "power_in"))
      (node (ref "U3") (pin "29_3") (pinfunction "GND_29_3") (pintype "power_in"))
      (node (ref "U3") (pin "29_4") (pinfunction "GND_29_4") (pintype "power_in"))
      (node (ref "U3") (pin "29_5") (pinfunction "GND_29_5") (pintype "power_in"))
      (node (ref "U3") (pin "29_6") (pinfunction "GND_29_6") (pintype "power_in"))
      (node (ref "U3") (pin "29_7") (pinfunction "GND_29_7") (pintype "power_in"))
      (node (ref "U3") (pin "29_8") (pinfunction "GND_29_8") (pintype "power_in"))
      (node (ref "U3") (pin "29_9") (pinfunction "GND_29_9") (pintype "power_in"))
      (node (ref "U4") (pin "1") (pinfunction "CTG_1") (pintype "power_in"))
      (node (ref "U4") (pin "4") (pinfunction "GND_4") (pintype "power_in"))
      (node (ref "U4") (pin "6") (pinfunction "QSTRT_6") (pintype "input"))
      (node (ref "U4") (pin "9") (pinfunction "EP_9") (pintype "power_in"))
      (node (ref "U5") (pin "13") (pinfunction "GND_13") (pintype "power_in"))
      (node (ref "U6") (pin "4") (pinfunction "GND_4") (pintype "power_in"))
      (node (ref "U6") (pin "9") (pinfunction "EXP_9") (pintype "passive"))
    )
    (net (code "14") (name "GPIO8") (class "Default")
      (node (ref "R3") (pin "1") (pinfunction "1_1") (pintype "passive"))
      (node (ref "U3") (pin "10") (pinfunction "IO8_10") (pintype "bidirectional"))
    )
    (net (code "15") (name "I2C_PW") (class "Default")
      (node (ref "C7") (pin "1") (pinfunction "1_1") (pintype "passive"))
      (node (ref "C8") (pin "1") (pinfunction "1_1") (pintype "passive"))
      (node (ref "R1_PINH") (pin "2") (pinfunction "2_2") (pintype "passive"))
      (node (ref "R2_PINH") (pin "2") (pinfunction "2_2") (pintype "passive"))
      (node (ref "U1") (pin "2") (pinfunction "CSB_2") (pintype "input"))
      (node (ref "U1") (pin "6") (pinfunction "VDDIO_6") (pintype "power_in"))
      (node (ref "U1") (pin "8") (pinfunction "VDD_8") (pintype "power_in"))
      (node (ref "U3") (pin "17") (pinfunction "IO19_17") (pintype "bidirectional"))
    )
    (net (code "16") (name "INT_RTC") (class "Default")
      (node (ref "R1_PINH1") (pin "1") (pinfunction "1_1") (pintype "passive"))
      (node (ref "RTC-PAD") (pin "TP") (pinfunction "TP_TP") (pintype "input"))
      (node (ref "U3") (pin "8") (pinfunction "IO0_8") (pintype "bidirectional"))
      (node (ref "U5") (pin "3") (pinfunction "SQW/~{INT}_3") (pintype "output"))
    )
    (net (code "17") (name "IO{slash}BOOT") (class "Default")
      (node (ref "BOOT_BTN") (pin "3") (pinfunction "3_3") (pintype "passive"))
      (node (ref "BOOT_BTN") (pin "4") (pinfunction "4_4") (pintype "passive"))
      (node (ref "C11") (pin "1") (pinfunction "1_1") (pintype "passive"))
      (node (ref "R6") (pin "1") (pinfunction "1_1") (pintype "passive"))
      (node (ref "U3") (pin "15") (pinfunction "IO9_15") (pintype "bidirectional"))
    )
    (net (code "18") (name "IO{slash}CHANGE") (class "Default")
      (node (ref "C12") (pin "1") (pinfunction "1_1") (pintype "passive"))
      (node (ref "R7") (pin "1") (pinfunction "1_1") (pintype "passive"))
      (node (ref "R_CHANGE") (pin "3") (pinfunction "3_3") (pintype "passive"))
      (node (ref "R_CHANGE") (pin "4") (pinfunction "4_4") (pintype "passive"))
      (node (ref "U3") (pin "23") (pinfunction "IO15_23") (pintype "bidirectional"))
    )
    (net (code "19") (name "MISO") (class "Default")
      (node (ref "D7") (pin "2") (pinfunction "2_2") (pintype "passive"))
      (node (ref "J2") (pin "P7") (pinfunction "DAT0_P7") (pintype "bidirectional"))
      (node (ref "MISO") (pin "TP") (pinfunction "TP_TP") (pintype "input"))
      (node (ref "R8") (pin "1") (pinfunction "1_1") (pintype "passive"))
      (node (ref "U3") (pin "27") (pinfunction "IO2_27") (pintype "bidirectional"))
      (node (ref "U6") (pin "2") (pinfunction "DO(IO1)_2") (pintype "bidirectional"))
    )
    (net (code "20") (name "MOSI") (class "Default")
      (node (ref "D8") (pin "2") (pinfunction "2_2") (pintype "passive"))
      (node (ref "J2") (pin "P3") (pinfunction "CMD_P3") (pintype "bidirectional"))
      (node (ref "J3") (pin "14") (pinfunction "14_14") (pintype "bidirectional"))
      (node (ref "MOSI") (pin "TP") (pinfunction "TP_TP") (pintype "input"))
      (node (ref "R9") (pin "1") (pinfunction "1_1") (pintype "passive"))
      (node (ref "U3") (pin "7") (pinfunction "IO7_7") (pintype "bidirectional"))
      (node (ref "U6") (pin "5") (pinfunction "DI(IO0)_5") (pintype "bidirectional"))
    )
    (net (code "21") (name "Net-(CHG_LED-PadC)") (class "Default")
      (node (ref "CHG_LED") (pin "C") (pinfunction "C_C") (pintype "passive"))
      (node (ref "R1_BAT") (pin "1") (pinfunction "1_1") (pintype "passive"))
    )
    (net (code "22") (name "Net-(D2-CATHODE)") (class "Default")
      (node (ref "C1_BAT1") (pin "1") (pinfunction "1_1") (pintype "passive"))
      (node (ref "D2") (pin "1") (pinfunction "CATHODE_1") (pintype "bidirectional"))
      (node (ref "IC1") (pin "1") (pinfunction "VIN_1") (pintype "bidirectional"))
      (node (ref "IC1") (pin "3") (pinfunction "CE_3") (pintype "bidirectional"))
      (node (ref "Q1") (pin "2") (pinfunction "S_2") (pintype "bidirectional"))
    )
    (net (code "23") (name "Net-(D3-A)") (class "Default")
      (node (ref "C5") (pin "1") (pinfunction "1_1") (pintype "passive"))
      (node (ref "D3") (pin "2") (pinfunction "A_2") (pintype "bidirectional"))
      (node (ref "D4") (pin "1") (pinfunction "K_1") (pintype "bidirectional"))
    )
    (net (code "24") (name "Net-(D6-CATHODE)") (class "Default")
      (node (ref "D6") (pin "1") (pinfunction "CATHODE_1") (pintype "bidirectional"))
      (node (ref "R_CAPACITOR") (pin "1") (pinfunction "1_1") (pintype "passive"))
    )
    (net (code "25") (name "Net-(EPD_C1-Pad2)") (class "Default")
      (node (ref "EPD_C1") (pin "2") (pinfunction "2_2") (pintype "passive"))
      (node (ref "J3") (pin "4") (pinfunction "4_4") (pintype "bidirectional"))
    )
    (net (code "26") (name "Net-(EPD_C2-Pad2)") (class "Default")
      (node (ref "EPD_C2") (pin "2") (pinfunction "2_2") (pintype "passive"))
      (node (ref "J3") (pin "5") (pinfunction "5_5") (pintype "bidirectional"))
    )
    (net (code "27") (name "Net-(EPD_C6-Pad1)") (class "Default")
      (node (ref "EPD_C6") (pin "1") (pinfunction "1_1") (pintype "passive"))
      (node (ref "J3") (pin "18") (pinfunction "18_18") (pintype "bidirectional"))
    )
    (net (code "28") (name "Net-(EPD_C7-Pad1)") (class "Default")
      (node (ref "EPD_C7") (pin "1") (pinfunction "1_1") (pintype "passive"))
      (node (ref "J3") (pin "19") (pinfunction "19_19") (pintype "bidirectional"))
    )
    (net (code "29") (name "Net-(EPD_C8-Pad1)") (class "Default")
      (node (ref "EPD_C8") (pin "1") (pinfunction "1_1") (pintype "passive"))
      (node (ref "J3") (pin "20") (pinfunction "20_20") (pintype "bidirectional"))
    )
    (net (code "30") (name "Net-(EPD_C10-Pad1)") (class "Default")
      (node (ref "EPD_C10") (pin "1") (pinfunction "1_1") (pintype "passive"))
      (node (ref "J3") (pin "22") (pinfunction "22_22") (pintype "bidirectional"))
    )
    (net (code "31") (name "Net-(EPD_C12-Pad1)") (class "Default")
      (node (ref "EPD_C12") (pin "1") (pinfunction "1_1") (pintype "passive"))
      (node (ref "J3") (pin "24") (pinfunction "24_24") (pintype "bidirectional"))
    )
    (net (code "32") (name "Net-(IC2-CT)") (class "Default")
      (node (ref "C_DELAY") (pin "1") (pinfunction "1_1") (pintype "passive"))
      (node (ref "IC2") (pin "5") (pinfunction "CT_5") (pintype "bidirectional"))
    )
    (net (code "33") (name "Net-(J1-PadA5)") (class "Default")
      (node (ref "J1") (pin "A5") (pinfunction "A5_A5") (pintype "bidirectional"))
      (node (ref "R2-USB1") (pin "2") (pinfunction "2_2") (pintype "passive"))
    )
    (net (code "34") (name "Net-(J1-PadB5)") (class "Default")
      (node (ref "J1") (pin "B5") (pinfunction "B5_B5") (pintype "bidirectional"))
      (node (ref "R2-USB") (pin "1") (pinfunction "1_1") (pintype "passive"))
    )
    (net (code "35") (name "Net-(U2-PROG)") (class "Default")
      (node (ref "R2_BAT") (pin "2") (pinfunction "2_2") (pintype "passive"))
      (node (ref "U2") (pin "5") (pinfunction "PROG_5") (pintype "input"))
    )
    (net (code "36") (name "Net-(U2-STAT)") (class "Default")
      (node (ref "R1_BAT") (pin "2") (pinfunction "2_2") (pintype "passive"))
      (node (ref "U2") (pin "1") (pinfunction "STAT_1") (pintype "output"))
    )
    (net (code "37") (name "Net-(U2-VIN)") (class "Default")
      (node (ref "C1_BAT") (pin "1") (pinfunction "1_1") (pintype "passive"))
      (node (ref "CHG_LED") (pin "A") (pinfunction "A_A") (pintype "passive"))
      (node (ref "U2") (pin "4") (pinfunction "VIN_4") (pintype "power_in"))
    )
    (net (code "38") (name "PREVGH") (class "Default")
      (node (ref "D5") (pin "1") (pinfunction "K_1") (pintype "bidirectional"))
      (node (ref "EPD_C9") (pin "1") (pinfunction "1_1") (pintype "passive"))
      (node (ref "J3") (pin "21") (pinfunction "21_21") (pintype "bidirectional"))
    )
    (net (code "39") (name "PREVGL") (class "Default")
      (node (ref "D4") (pin "2") (pinfunction "A_2") (pintype "bidirectional"))
      (node (ref "EPD_C11") (pin "1") (pinfunction "1_1") (pintype "passive"))
      (node (ref "J3") (pin "23") (pinfunction "23_23") (pintype "bidirectional"))
    )
    (net (code "40") (name "RESE") (class "Default")
      (node (ref "J3") (pin "3") (pinfunction "3_3") (pintype "bidirectional"))
      (node (ref "Q2") (pin "2") (pinfunction "S_2") (pintype "bidirectional"))
      (node (ref "R2") (pin "2") (pinfunction "2_2") (pintype "passive"))
    )
    (net (code "41") (name "RESE'") (class "Default")
      (node (ref "R2") (pin "1") (pinfunction "1_1") (pintype "passive"))
      (node (ref "R4") (pin "2") (pinfunction "2_2") (pintype "passive"))
      (node (ref "SJ1") (pin "2") (pinfunction "2_2") (pintype "passive"))
    )
    (net (code "42") (name "RESET") (class "Default")
      (node (ref "C10") (pin "1") (pinfunction "1_1") (pintype "passive"))
      (node (ref "IC2") (pin "1") (pinfunction "VOUT_1") (pintype "bidirectional"))
      (node (ref "R5") (pin "1") (pinfunction "1_1") (pintype "passive"))
      (node (ref "RESET_BTN") (pin "3") (pinfunction "3_3") (pintype "passive"))
      (node (ref "RESET_BTN") (pin "4") (pinfunction "4_4") (pintype "passive"))
      (node (ref "U3") (pin "3") (pinfunction "EN_3") (pintype "input"))
    )
    (net (code "43") (name "RTC_RST") (class "Default")
      (node (ref "U3") (pin "16") (pinfunction "IO18_16") (pintype "bidirectional"))
      (node (ref "U5") (pin "4") (pinfunction "~{RST}_4") (pintype "input"))
    )
    (net (code "44") (name "RX") (class "Default")
      (node (ref "TP2") (pin "TP") (pinfunction "TP_TP") (pintype "input"))
      (node (ref "U3") (pin "24") (pinfunction "RXD0/GPIO17_24") (pintype "bidirectional"))
    )
    (net (code "45") (name "SCK") (class "Default")
      (node (ref "D9") (pin "2") (pinfunction "2_2") (pintype "passive"))
      (node (ref "J2") (pin "P5") (pinfunction "CLK_P5") (pintype "bidirectional"))
      (node (ref "J3") (pin "13") (pinfunction "13_13") (pintype "bidirectional"))
      (node (ref "R10") (pin "1") (pinfunction "1_1") (pintype "passive"))
      (node (ref "SCK") (pin "TP") (pinfunction "TP_TP") (pintype "input"))
      (node (ref "U3") (pin "6") (pinfunction "IO6_6") (pintype "bidirectional"))
      (node (ref "U6") (pin "6") (pinfunction "CLK_6") (pintype "input"))
    )
    (net (code "46") (name "SCL") (class "Default")
      (node (ref "J4") (pin "4") (pinfunction "4_4") (pintype "passive"))
      (node (ref "R2_PINH") (pin "1") (pinfunction "1_1") (pintype "passive"))
      (node (ref "U1") (pin "4") (pinfunction "SCK_4") (pintype "input"))
      (node (ref "U3") (pin "20") (pinfunction "IO22_20") (pintype "bidirectional"))
      (node (ref "U4") (pin "7") (pinfunction "SCL_7") (pintype "input"))
      (node (ref "U5") (pin "16") (pinfunction "SCL_16") (pintype "input"))
    )
    (net (code "47") (name "SDA") (class "Default")
      (node (ref "J4") (pin "3") (pinfunction "3_3") (pintype "passive"))
      (node (ref "R1_PINH") (pin "1") (pinfunction "1_1") (pintype "passive"))
      (node (ref "U1") (pin "3") (pinfunction "SDI_3") (pintype "bidirectional"))
      (node (ref "U3") (pin "19") (pinfunction "IO21_19") (pintype "bidirectional"))
      (node (ref "U4") (pin "8") (pinfunction "SDA_8") (pintype "bidirectional"))
      (node (ref "U5") (pin "15") (pinfunction "SDA_15") (pintype "bidirectional"))
    )
    (net (code "48") (name "SRC") (class "Default")
      (node (ref "C5") (pin "2") (pinfunction "2_2") (pintype "passive"))
      (node (ref "D5") (pin "2") (pinfunction "A_2") (pintype "bidirectional"))
      (node (ref "L1") (pin "1") (pinfunction "1_1") (pintype "passive"))
      (node (ref "Q2") (pin "3") (pinfunction "D_3") (pintype "bidirectional"))
    )
    (net (code "49") (name "SS_SD") (class "Default")
      (node (ref "D12") (pin "2") (pinfunction "2_2") (pintype "passive"))
      (node (ref "J2") (pin "P2") (pinfunction "CD/DAT3_P2") (pintype "bidirectional"))
      (node (ref "R13") (pin "1") (pinfunction "1_1") (pintype "passive"))
      (node (ref "U3") (pin "4") (pinfunction "IO4_4") (pintype "bidirectional"))
    )
    (net (code "50") (name "TX") (class "Default")
      (node (ref "TP1") (pin "TP") (pinfunction "TP_TP") (pintype "input"))
      (node (ref "U3") (pin "25") (pinfunction "TXD0/GPIO16_25") (pintype "bidirectional"))
    )
    (net (code "51") (name "USB_D+") (class "Default")
      (node (ref "D1") (pin "4") (pinfunction "I/O2_2_4") (pintype "bidirectional"))
      (node (ref "U3") (pin "14") (pinfunction "IO13_14") (pintype "bidirectional"))
    )
    (net (code "52") (name "USB_D-") (class "Default")
      (node (ref "D1") (pin "6") (pinfunction "I/O1_2_6") (pintype "bidirectional"))
      (node (ref "U3") (pin "13") (pinfunction "IO12_13") (pintype "bidirectional"))
    )
    (net (code "53") (name "VBAT") (class "Default")
      (node (ref "C2_BAT") (pin "1") (pinfunction "1_1") (pintype "passive"))
      (node (ref "Q1") (pin "3") (pinfunction "D_3") (pintype "bidirectional"))
      (node (ref "U2") (pin "3") (pinfunction "VBAT_3") (pintype "power_in"))
      (node (ref "U4") (pin "2") (pinfunction "CELL_2") (pintype "power_in"))
      (node (ref "U4") (pin "3") (pinfunction "VDD_3") (pintype "power_in"))
      (node (ref "VBAT-PAD") (pin "TP") (pinfunction "TP_TP") (pintype "input"))
    )
    (net (code "54") (name "VBUS") (class "Default")
      (node (ref "C1") (pin "1") (pinfunction "1_1") (pintype "passive"))
      (node (ref "C2") (pin "1") (pinfunction "1_1") (pintype "passive"))
      (node (ref "D1") (pin "2") (pinfunction "GND_2") (pintype "bidirectional"))
      (node (ref "D2") (pin "2") (pinfunction "ANODE_2") (pintype "bidirectional"))
      (node (ref "PFMF.050.1") (pin "2") (pinfunction "2_2") (pintype "passive"))
      (node (ref "Q1") (pin "1") (pinfunction "G_1") (pintype "bidirectional"))
      (node (ref "R1_PWRUSB") (pin "2") (pinfunction "2_2") (pintype "passive"))
      (node (ref "VBUS-PAD") (pin "TP") (pinfunction "TP_TP") (pintype "input"))
    )
    (net (code "55") (name "VRTC") (class "Default")
      (node (ref "C13_SUPERCAP") (pin "1") (pinfunction "1_1") (pintype "passive"))
      (node (ref "C9") (pin "1") (pinfunction "1_1") (pintype "passive"))
      (node (ref "R_CAPACITOR") (pin "2") (pinfunction "2_2") (pintype "passive"))
      (node (ref "U5") (pin "14") (pinfunction "VBAT_14") (pintype "power_in"))
    )
    (net (code "56") (name "VUSB") (class "Default")
      (node (ref "J1") (pin "A4") (pinfunction "A4_A4") (pintype "bidirectional"))
      (node (ref "J1") (pin "A9") (pinfunction "A9_A9") (pintype "bidirectional"))
      (node (ref "J1") (pin "B4") (pinfunction "B4_B4") (pintype "bidirectional"))
      (node (ref "J1") (pin "B9") (pinfunction "B9_B9") (pintype "bidirectional"))
      (node (ref "PFMF.050.1") (pin "1") (pinfunction "1_1") (pintype "passive"))
    )
    (net (code "57") (name "unconnected-(IC1-NC-Pad4)") (class "Default")
      (node (ref "IC1") (pin "4") (pinfunction "NC_4") (pintype "no_connect"))
    )
    (net (code "58") (name "unconnected-(IC2-NC-Pad4)") (class "Default")
      (node (ref "IC2") (pin "4") (pinfunction "NC_4") (pintype "no_connect"))
    )
    (net (code "59") (name "unconnected-(J1-PadA8)") (class "Default")
      (node (ref "J1") (pin "A8") (pinfunction "A8_A8") (pintype "bidirectional"))
    )
    (net (code "60") (name "unconnected-(J1-PadB8)") (class "Default")
      (node (ref "J1") (pin "B8") (pinfunction "B8_B8") (pintype "bidirectional"))
    )
    (net (code "61") (name "unconnected-(J2-DAT1-PadP8)") (class "Default")
      (node (ref "J2") (pin "P8") (pinfunction "DAT1_P8") (pintype "bidirectional"))
    )
    (net (code "62") (name "unconnected-(J2-DAT2-PadP1)") (class "Default")
      (node (ref "J2") (pin "P1") (pinfunction "DAT2_P1") (pintype "bidirectional"))
    )
    (net (code "63") (name "unconnected-(J2-DETECTION_1-PadS1)") (class "Default")
      (node (ref "J2") (pin "S1") (pinfunction "DETECTION_1_S1") (pintype "bidirectional"))
    )
    (net (code "64") (name "unconnected-(J2-DETECTION_2-PadS2)") (class "Default")
      (node (ref "J2") (pin "S2") (pinfunction "DETECTION_2_S2") (pintype "bidirectional"))
    )
    (net (code "65") (name "unconnected-(J3-Pad1)") (class "Default")
      (node (ref "J3") (pin "1") (pinfunction "1_1") (pintype "bidirectional"))
    )
    (net (code "66") (name "unconnected-(J3-Pad6)") (class "Default")
      (node (ref "J3") (pin "6") (pinfunction "6_6") (pintype "bidirectional"))
    )
    (net (code "67") (name "unconnected-(J3-Pad7)") (class "Default")
      (node (ref "J3") (pin "7") (pinfunction "7_7") (pintype "bidirectional"))
    )
    (net (code "68") (name "unconnected-(U3-NC-Pad22)") (class "Default")
      (node (ref "U3") (pin "22") (pinfunction "NC_22") (pintype "no_connect"))
    )
    (net (code "69") (name "unconnected-(U4-~{ALERT}-Pad5)") (class "Default")
      (node (ref "U4") (pin "5") (pinfunction "~{ALERT}_5") (pintype "output"))
    )
  )
)
